# TuringGatesBuffer.net
KiCad netlist of a schematic drawn in EAGLE
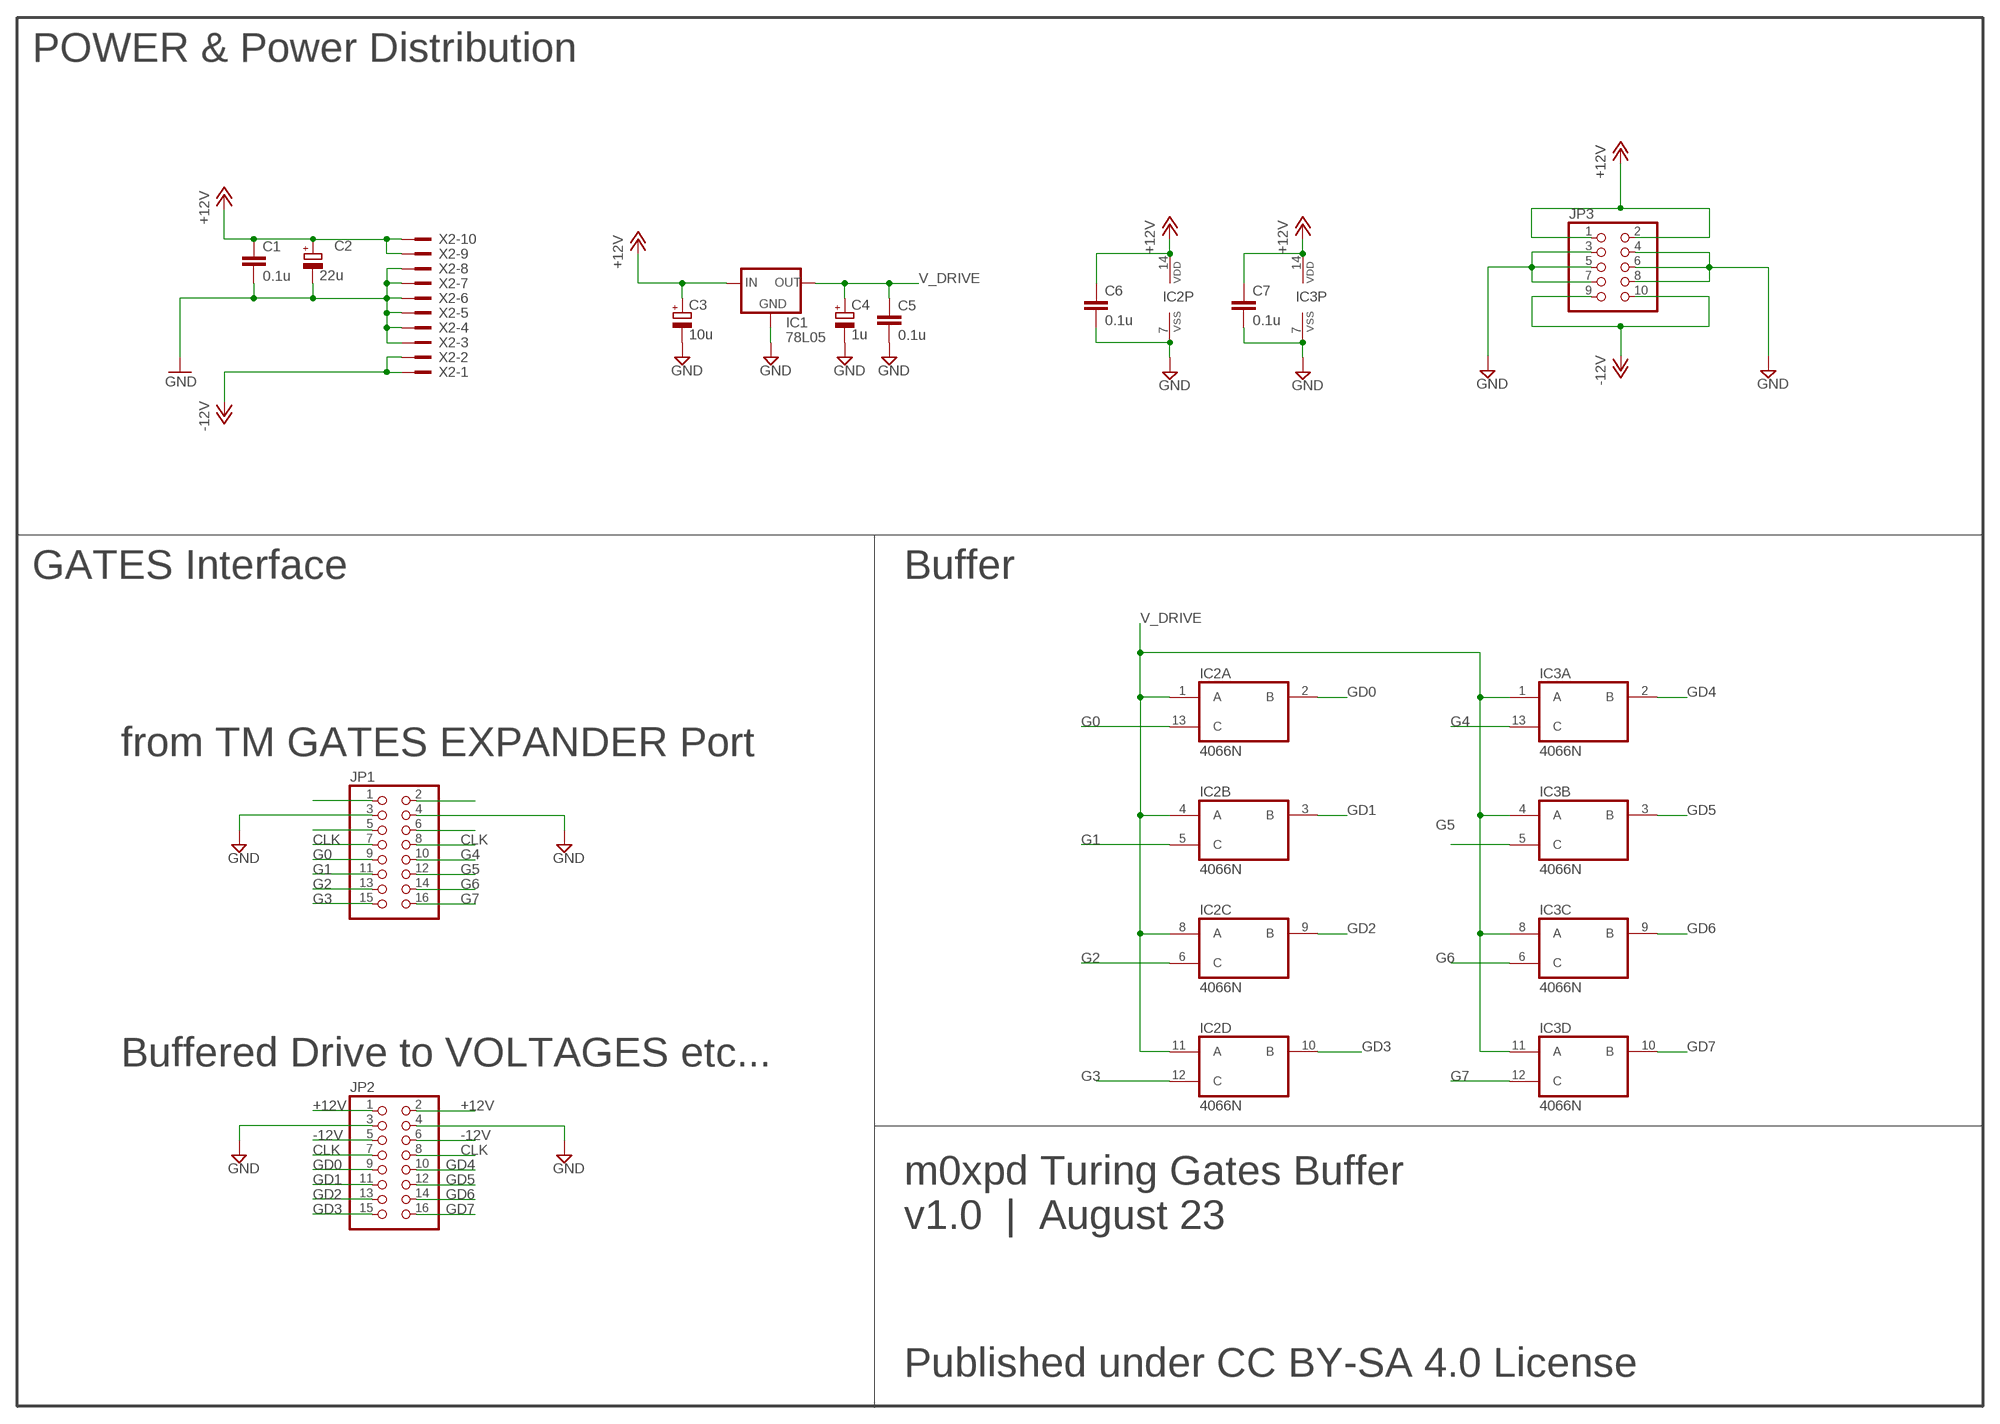
[diagram p0: schematic, sheet 1]

(export (version "E")
  (design (tool "Eeschema 10.0.6"))
  (components
    (comp (ref "C1")
      (value "0.1u")
      (footprint "eagle-import:C050-025X075")
      (libsource (lib "eagle-import") (part "C-EU050-025X075"))
    )
    (comp (ref "C2")
      (value "22u")
      (footprint "eagle-import:E2,5-5")
      (libsource (lib "eagle-import") (part "CPOL-EUE2.5-5"))
    )
    (comp (ref "C3")
      (value "10u")
      (footprint "eagle-import:E2,5-5")
      (libsource (lib "eagle-import") (part "CPOL-EUE2.5-5"))
    )
    (comp (ref "C4")
      (value "1u")
      (footprint "eagle-import:E2,5-5")
      (libsource (lib "eagle-import") (part "CPOL-EUE2.5-5"))
    )
    (comp (ref "C5")
      (value "0.1u")
      (footprint "eagle-import:C050-025X075")
      (libsource (lib "eagle-import") (part "C-EU050-025X075"))
    )
    (comp (ref "C6")
      (value "0.1u")
      (footprint "eagle-import:C050-025X075")
      (libsource (lib "eagle-import") (part "C-EU050-025X075"))
    )
    (comp (ref "C7")
      (value "0.1u")
      (footprint "eagle-import:C050-025X075")
      (libsource (lib "eagle-import") (part "C-EU050-025X075"))
    )
    (comp (ref "IC1")
      (value "78L05")
      (footprint "eagle-import:78LXX")
      (libsource (lib "eagle-import") (part "78LXX"))
    )
    (comp (ref "IC2")
      (value "4066N")
      (footprint "eagle-import:DIL14")
      (libsource (lib "eagle-import") (part "4066N"))
    )
    (comp (ref "IC3")
      (value "4066N")
      (footprint "eagle-import:DIL14")
      (libsource (lib "eagle-import") (part "4066N"))
    )
    (comp (ref "JP1")
      (value "PINHD-2X8")
      (footprint "eagle-import:2X08")
      (libsource (lib "eagle-import") (part "PINHD-2X8"))
    )
    (comp (ref "JP2")
      (value "PINHD-2X8")
      (footprint "eagle-import:2X08")
      (libsource (lib "eagle-import") (part "PINHD-2X8"))
    )
    (comp (ref "JP3")
      (value "PINHD-2X5")
      (footprint "eagle-import:2X05")
      (libsource (lib "eagle-import") (part "PINHD-2X5"))
    )
    (comp (ref "X2")
      (value "2510-")
      (footprint "eagle-import:PAK100_2500-10")
      (fields (field (name "MF") "3M") (field (name "MPN") "2510-6002UB"))
      (libsource (lib "eagle-import") (part "2510-"))
    )
  )
  (nets
    (net (code "1") (name "+12V") (class "Default")
      (node (ref "C1") (pin "1") (pinfunction "1_1") (pintype "passive"))
      (node (ref "C2") (pin "+") (pinfunction "+_+") (pintype "passive"))
      (node (ref "C3") (pin "+") (pinfunction "+_+") (pintype "passive"))
      (node (ref "C6") (pin "1") (pinfunction "1_1") (pintype "passive"))
      (node (ref "C7") (pin "1") (pinfunction "1_1") (pintype "passive"))
      (node (ref "IC1") (pin "IN") (pinfunction "IN_IN") (pintype "input"))
      (node (ref "IC2") (pin "14") (pinfunction "VDD_14") (pintype "power_in"))
      (node (ref "IC3") (pin "14") (pinfunction "VDD_14") (pintype "power_in"))
      (node (ref "JP2") (pin "1") (pinfunction "1_1") (pintype "passive"))
      (node (ref "JP2") (pin "2") (pinfunction "2_2") (pintype "passive"))
      (node (ref "JP3") (pin "1") (pinfunction "1_1") (pintype "passive"))
      (node (ref "JP3") (pin "2") (pinfunction "2_2") (pintype "passive"))
      (node (ref "X2") (pin "10") (pinfunction "KL_10") (pintype "passive"))
      (node (ref "X2") (pin "9") (pinfunction "KL_9") (pintype "passive"))
    )
    (net (code "2") (name "-12V") (class "Default")
      (node (ref "JP2") (pin "5") (pinfunction "5_5") (pintype "passive"))
      (node (ref "JP2") (pin "6") (pinfunction "6_6") (pintype "passive"))
      (node (ref "JP3") (pin "10") (pinfunction "10_10") (pintype "passive"))
      (node (ref "JP3") (pin "9") (pinfunction "9_9") (pintype "passive"))
      (node (ref "X2") (pin "1") (pinfunction "KL_1") (pintype "passive"))
      (node (ref "X2") (pin "2") (pinfunction "KL_2") (pintype "passive"))
    )
    (net (code "3") (name "/CLK") (class "Default")
      (node (ref "JP1") (pin "7") (pinfunction "7_7") (pintype "passive"))
      (node (ref "JP1") (pin "8") (pinfunction "8_8") (pintype "passive"))
      (node (ref "JP2") (pin "7") (pinfunction "7_7") (pintype "passive"))
      (node (ref "JP2") (pin "8") (pinfunction "8_8") (pintype "passive"))
    )
    (net (code "4") (name "/G0") (class "Default")
      (node (ref "IC2") (pin "13") (pinfunction "C_13") (pintype "input"))
      (node (ref "JP1") (pin "9") (pinfunction "9_9") (pintype "passive"))
    )
    (net (code "5") (name "/G1") (class "Default")
      (node (ref "IC2") (pin "5") (pinfunction "C_5") (pintype "input"))
      (node (ref "JP1") (pin "11") (pinfunction "11_11") (pintype "passive"))
    )
    (net (code "6") (name "/G2") (class "Default")
      (node (ref "IC2") (pin "6") (pinfunction "C_6") (pintype "input"))
      (node (ref "JP1") (pin "13") (pinfunction "13_13") (pintype "passive"))
    )
    (net (code "7") (name "/G3") (class "Default")
      (node (ref "IC2") (pin "12") (pinfunction "C_12") (pintype "input"))
      (node (ref "JP1") (pin "15") (pinfunction "15_15") (pintype "passive"))
    )
    (net (code "8") (name "/G4") (class "Default")
      (node (ref "IC3") (pin "13") (pinfunction "C_13") (pintype "input"))
      (node (ref "JP1") (pin "10") (pinfunction "10_10") (pintype "passive"))
    )
    (net (code "9") (name "/G5") (class "Default")
      (node (ref "IC3") (pin "5") (pinfunction "C_5") (pintype "input"))
      (node (ref "JP1") (pin "12") (pinfunction "12_12") (pintype "passive"))
    )
    (net (code "10") (name "/G6") (class "Default")
      (node (ref "IC3") (pin "6") (pinfunction "C_6") (pintype "input"))
      (node (ref "JP1") (pin "14") (pinfunction "14_14") (pintype "passive"))
    )
    (net (code "11") (name "/G7") (class "Default")
      (node (ref "IC3") (pin "12") (pinfunction "C_12") (pintype "input"))
      (node (ref "JP1") (pin "16") (pinfunction "16_16") (pintype "passive"))
    )
    (net (code "12") (name "/GD0") (class "Default")
      (node (ref "IC2") (pin "2") (pinfunction "B_2") (pintype "tri_state"))
      (node (ref "JP2") (pin "9") (pinfunction "9_9") (pintype "passive"))
    )
    (net (code "13") (name "/GD1") (class "Default")
      (node (ref "IC2") (pin "3") (pinfunction "B_3") (pintype "tri_state"))
      (node (ref "JP2") (pin "11") (pinfunction "11_11") (pintype "passive"))
    )
    (net (code "14") (name "/GD2") (class "Default")
      (node (ref "IC2") (pin "9") (pinfunction "B_9") (pintype "tri_state"))
      (node (ref "JP2") (pin "13") (pinfunction "13_13") (pintype "passive"))
    )
    (net (code "15") (name "/GD3") (class "Default")
      (node (ref "IC2") (pin "10") (pinfunction "B_10") (pintype "tri_state"))
      (node (ref "JP2") (pin "15") (pinfunction "15_15") (pintype "passive"))
    )
    (net (code "16") (name "/GD4") (class "Default")
      (node (ref "IC3") (pin "2") (pinfunction "B_2") (pintype "tri_state"))
      (node (ref "JP2") (pin "10") (pinfunction "10_10") (pintype "passive"))
    )
    (net (code "17") (name "/GD5") (class "Default")
      (node (ref "IC3") (pin "3") (pinfunction "B_3") (pintype "tri_state"))
      (node (ref "JP2") (pin "12") (pinfunction "12_12") (pintype "passive"))
    )
    (net (code "18") (name "/GD6") (class "Default")
      (node (ref "IC3") (pin "9") (pinfunction "B_9") (pintype "tri_state"))
      (node (ref "JP2") (pin "14") (pinfunction "14_14") (pintype "passive"))
    )
    (net (code "19") (name "/GD7") (class "Default")
      (node (ref "IC3") (pin "10") (pinfunction "B_10") (pintype "tri_state"))
      (node (ref "JP2") (pin "16") (pinfunction "16_16") (pintype "passive"))
    )
    (net (code "20") (name "/V_DRIVE") (class "Default")
      (node (ref "C4") (pin "+") (pinfunction "+_+") (pintype "passive"))
      (node (ref "C5") (pin "1") (pinfunction "1_1") (pintype "passive"))
      (node (ref "IC1") (pin "OUT") (pinfunction "OUT_OUT") (pintype "passive"))
      (node (ref "IC2") (pin "1") (pinfunction "A_1") (pintype "tri_state"))
      (node (ref "IC2") (pin "11") (pinfunction "A_11") (pintype "tri_state"))
      (node (ref "IC2") (pin "4") (pinfunction "A_4") (pintype "tri_state"))
      (node (ref "IC2") (pin "8") (pinfunction "A_8") (pintype "tri_state"))
      (node (ref "IC3") (pin "1") (pinfunction "A_1") (pintype "tri_state"))
      (node (ref "IC3") (pin "11") (pinfunction "A_11") (pintype "tri_state"))
      (node (ref "IC3") (pin "4") (pinfunction "A_4") (pintype "tri_state"))
      (node (ref "IC3") (pin "8") (pinfunction "A_8") (pintype "tri_state"))
    )
    (net (code "21") (name "GND") (class "Default")
      (node (ref "C1") (pin "2") (pinfunction "2_2") (pintype "passive"))
      (node (ref "C2") (pin "-") (pinfunction "-_-") (pintype "passive"))
      (node (ref "C3") (pin "-") (pinfunction "-_-") (pintype "passive"))
      (node (ref "C4") (pin "-") (pinfunction "-_-") (pintype "passive"))
      (node (ref "C5") (pin "2") (pinfunction "2_2") (pintype "passive"))
      (node (ref "C6") (pin "2") (pinfunction "2_2") (pintype "passive"))
      (node (ref "C7") (pin "2") (pinfunction "2_2") (pintype "passive"))
      (node (ref "IC1") (pin "GND") (pinfunction "GND_GND") (pintype "input"))
      (node (ref "IC2") (pin "7") (pinfunction "VSS_7") (pintype "power_in"))
      (node (ref "IC3") (pin "7") (pinfunction "VSS_7") (pintype "power_in"))
      (node (ref "JP1") (pin "3") (pinfunction "3_3") (pintype "passive"))
      (node (ref "JP1") (pin "4") (pinfunction "4_4") (pintype "passive"))
      (node (ref "JP2") (pin "3") (pinfunction "3_3") (pintype "passive"))
      (node (ref "JP2") (pin "4") (pinfunction "4_4") (pintype "passive"))
      (node (ref "JP3") (pin "3") (pinfunction "3_3") (pintype "passive"))
      (node (ref "JP3") (pin "4") (pinfunction "4_4") (pintype "passive"))
      (node (ref "JP3") (pin "5") (pinfunction "5_5") (pintype "passive"))
      (node (ref "JP3") (pin "6") (pinfunction "6_6") (pintype "passive"))
      (node (ref "JP3") (pin "7") (pinfunction "7_7") (pintype "passive"))
      (node (ref "JP3") (pin "8") (pinfunction "8_8") (pintype "passive"))
      (node (ref "X2") (pin "3") (pinfunction "KL_3") (pintype "passive"))
      (node (ref "X2") (pin "4") (pinfunction "KL_4") (pintype "passive"))
      (node (ref "X2") (pin "5") (pinfunction "KL_5") (pintype "passive"))
      (node (ref "X2") (pin "6") (pinfunction "KL_6") (pintype "passive"))
      (node (ref "X2") (pin "7") (pinfunction "KL_7") (pintype "passive"))
      (node (ref "X2") (pin "8") (pinfunction "KL_8") (pintype "passive"))
    )
    (net (code "22") (name "unconnected-(JP1-Pad1)") (class "Default")
      (node (ref "JP1") (pin "1") (pinfunction "1_1") (pintype "passive"))
    )
    (net (code "23") (name "unconnected-(JP1-Pad2)") (class "Default")
      (node (ref "JP1") (pin "2") (pinfunction "2_2") (pintype "passive"))
    )
    (net (code "24") (name "unconnected-(JP1-Pad5)") (class "Default")
      (node (ref "JP1") (pin "5") (pinfunction "5_5") (pintype "passive"))
    )
    (net (code "25") (name "unconnected-(JP1-Pad6)") (class "Default")
      (node (ref "JP1") (pin "6") (pinfunction "6_6") (pintype "passive"))
    )
  )
)
